# Trinity_Flight_Computer_2025-07-16.net
KiCad netlist of a schematic drawn in EasyEDA Pro
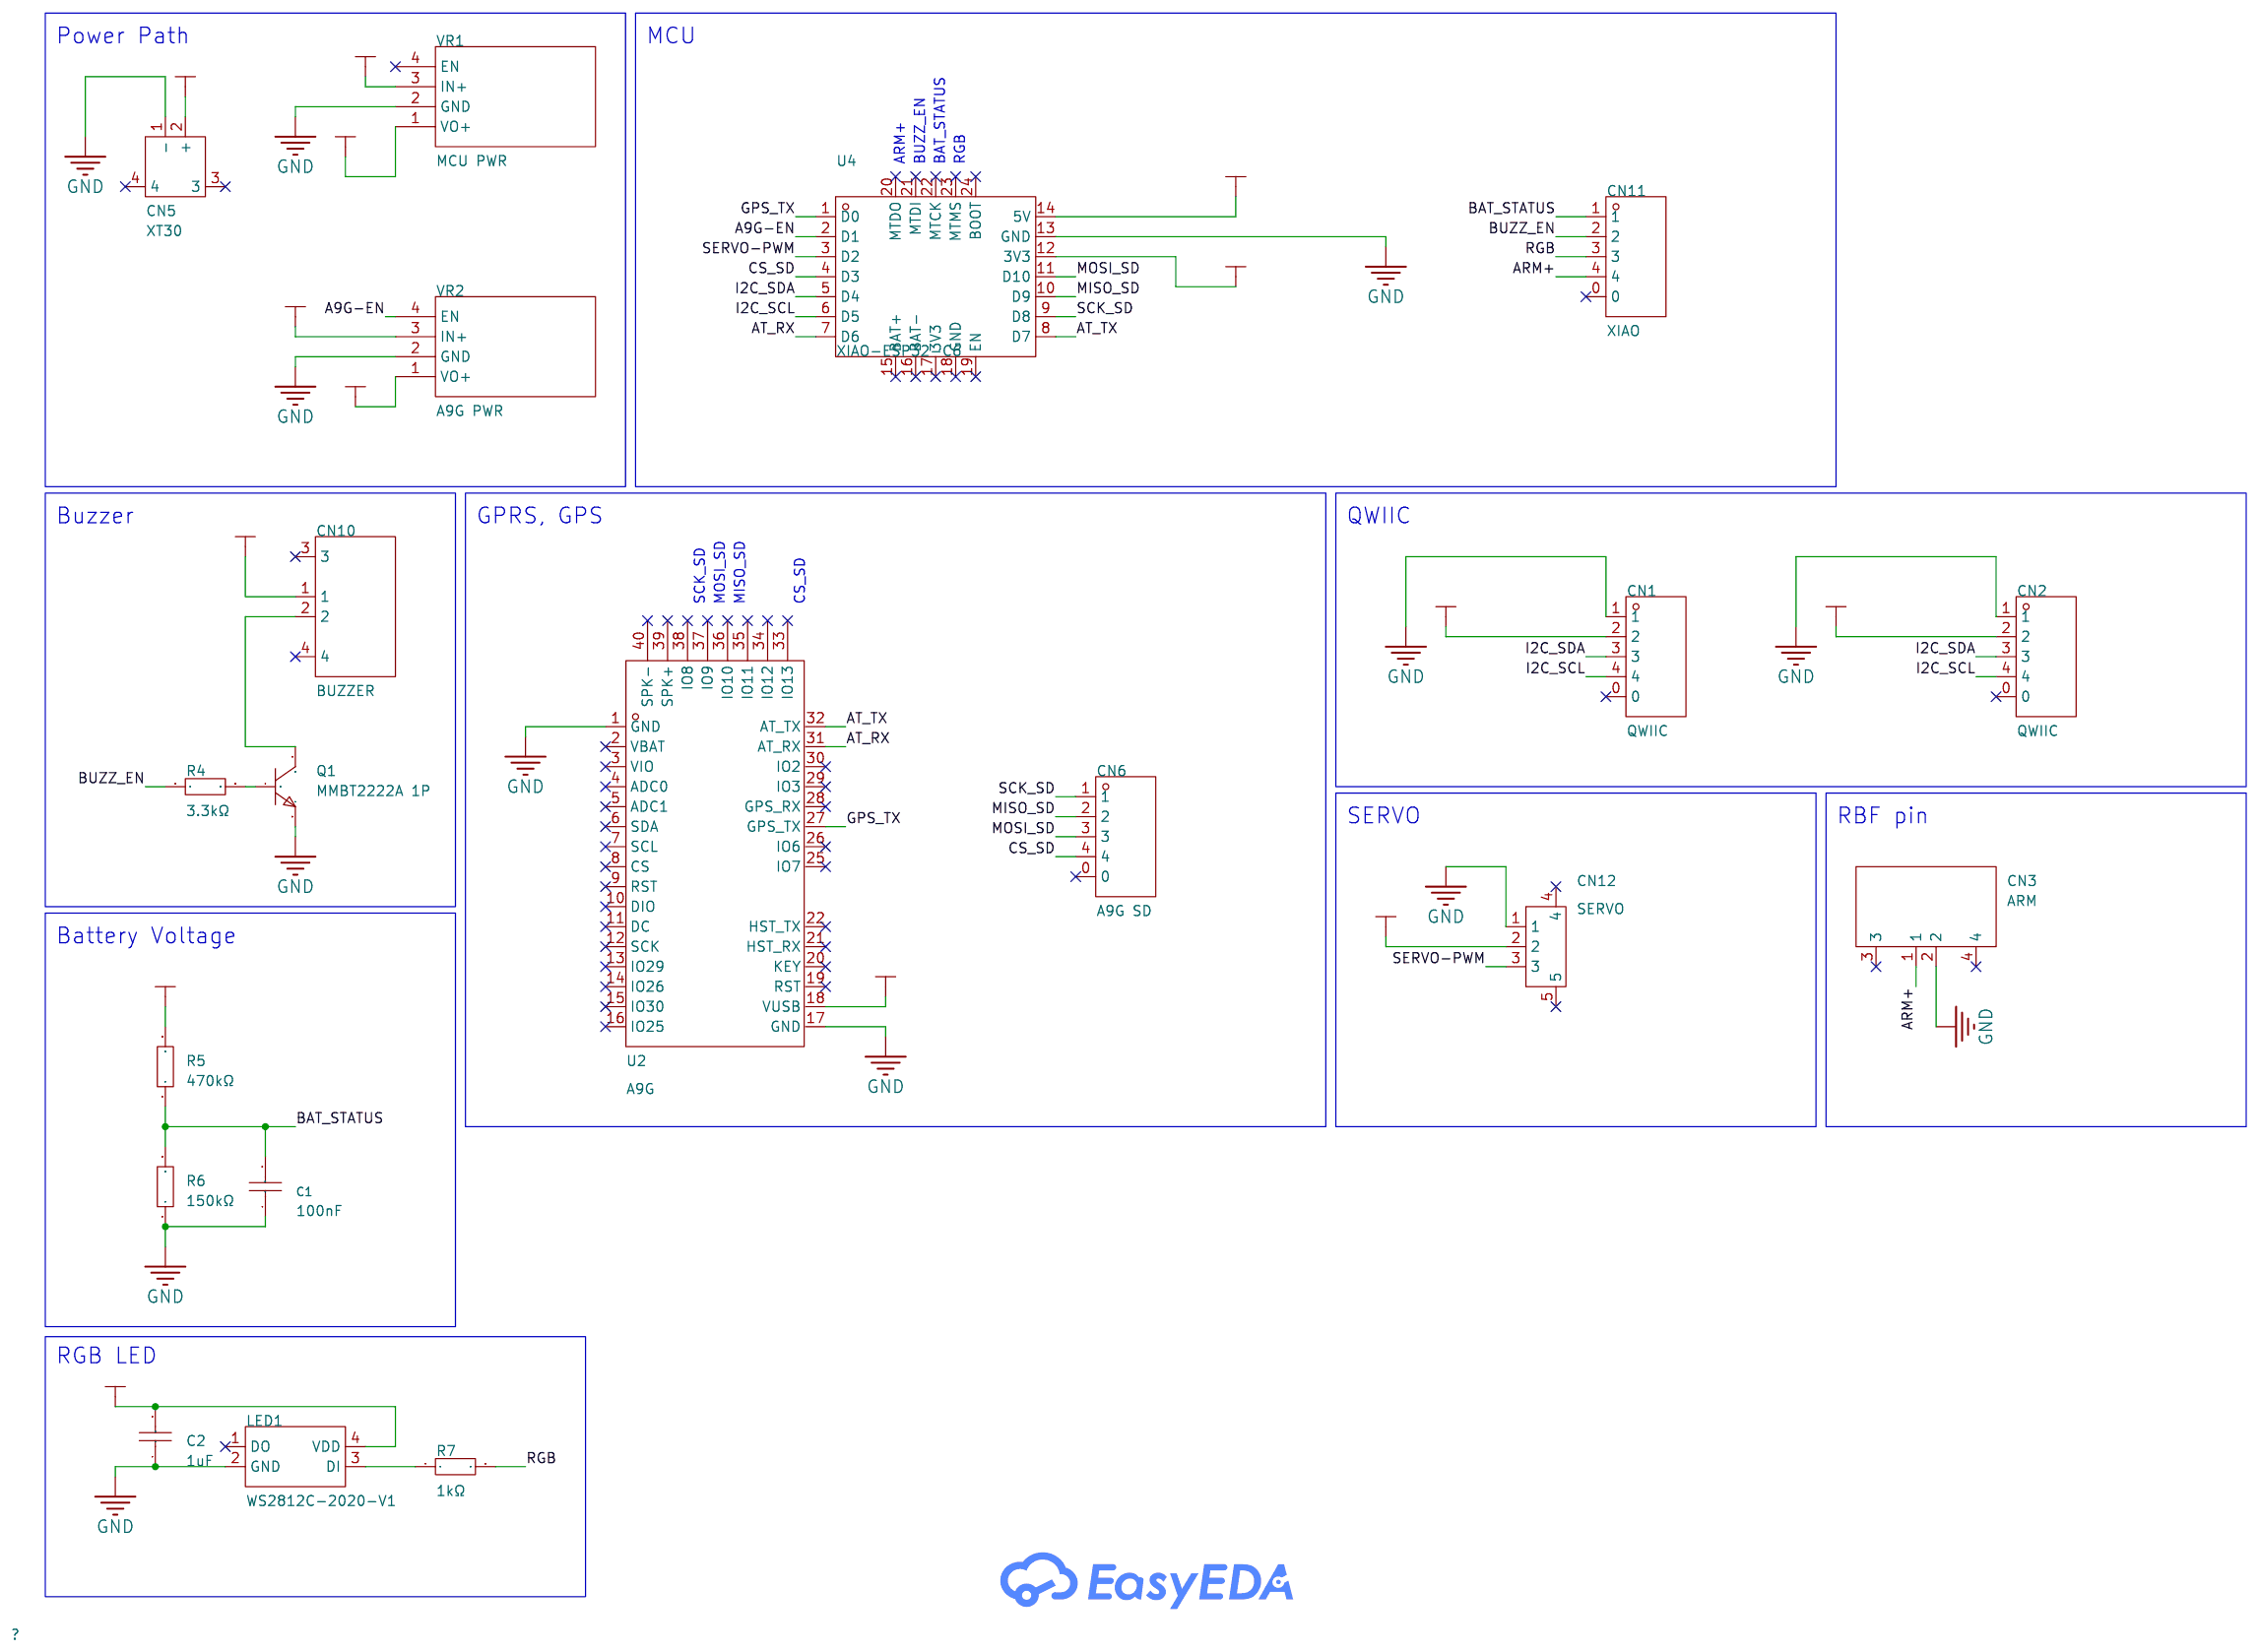
[diagram p0: schematic sheet]

(export (version "E")
  (design (tool "Eeschema 10.0.6"))
  (components
    (comp (ref "C1")
      (value "100nF")
      (footprint "easyedapro:C0603")
      (fields (field (name "Manufacturer Part") "0603B104K250CT") (field (name "Manufacturer") "Walsin(华新科)"))
      (libsource (lib "easyedapro") (part "0603B104K250"))
    )
    (comp (ref "C2")
      (value "1uF")
      (footprint "easyedapro:C0603")
      (fields (field (name "Manufacturer Part") "0603B105K160CT") (field (name "Manufacturer") "Walsin(华新科)"))
      (libsource (lib "easyedapro") (part "0603B105K160"))
    )
    (comp (ref "CN1")
      (value "QWIIC")
      (footprint "easyedapro:CONN-SMD_BM04B-SRSS-TB")
      (fields (field (name "Manufacturer Part") "BM04B-SRSS-TB(LF)(SN)") (field (name "Manufacturer") "JST"))
      (libsource (lib "easyedapro") (part "BM04B-SRSS-TB(LF)(SN)"))
    )
    (comp (ref "CN2")
      (value "QWIIC")
      (footprint "easyedapro:CONN-SMD_BM04B-SRSS-TB")
      (fields (field (name "Manufacturer Part") "BM04B-SRSS-TB(LF)(SN)") (field (name "Manufacturer") "JST"))
      (libsource (lib "easyedapro") (part "BM04B-SRSS-TB(LF)(SN)"))
    )
    (comp (ref "CN3")
      (value "ARM")
      (footprint "easyedapro:CONN-TH_BM02B-SRSS-TB-LF-SN")
      (fields (field (name "Manufacturer Part") "BM02B-SRSS-TB(LF)(SN)") (field (name "Manufacturer") "JST"))
      (libsource (lib "easyedapro") (part "BM02B-SRSS-TB (LF)(SN)"))
    )
    (comp (ref "CN5")
      (value "XT30")
      (footprint "easyedapro:CONN-TH_XT30PW-M")
      (fields (field (name "Manufacturer Part") "XT30PW-M30.G.Y") (field (name "Manufacturer") "AMASS(艾迈斯)"))
      (libsource (lib "easyedapro") (part "XT30PW-M"))
    )
    (comp (ref "CN6")
      (value "A9G SD")
      (footprint "easyedapro:CONN-SMD_BM04B-SRSS-TB")
      (fields (field (name "Manufacturer Part") "BM04B-SRSS-TB(LF)(SN)") (field (name "Manufacturer") "JST"))
      (libsource (lib "easyedapro") (part "BM04B-SRSS-TB(LF)(SN)"))
    )
    (comp (ref "CN10")
      (value "BUZZER")
      (footprint "easyedapro:CONN-TH_BM02B-SRSS-TB-LF-SN")
      (fields (field (name "Manufacturer Part") "BM02B-SRSS-TB(LF)(SN)") (field (name "Manufacturer") "JST"))
      (libsource (lib "easyedapro") (part "BM02B-SRSS-TB (LF)(SN)"))
    )
    (comp (ref "CN11")
      (value "XIAO")
      (footprint "easyedapro:CONN-SMD_BM04B-SRSS-TB")
      (fields (field (name "Manufacturer Part") "BM04B-SRSS-TB(LF)(SN)") (field (name "Manufacturer") "JST"))
      (libsource (lib "easyedapro") (part "BM04B-SRSS-TB(LF)(SN)"))
    )
    (comp (ref "CN12")
      (value "SERVO")
      (footprint "easyedapro:CONN-SMD_BM03B-SRSS-TBT-LF-SN")
      (fields (field (name "Manufacturer Part") "BM03B-SRSS-TBT(LF)(SN)") (field (name "Manufacturer") "JST"))
      (libsource (lib "easyedapro") (part "BM03B-SRSS-TBT(LF)(SN)"))
    )
    (comp (ref "LED1")
      (value "WS2812C-2020-V1")
      (footprint "easyedapro:LED-SMD_4P-L2.0-W2.0-TL_WS2812B-2020")
      (fields (field (name "Manufacturer") "worldsemi"))
      (libsource (lib "easyedapro") (part "WS2812C-2020-V1"))
    )
    (comp (ref "Q1")
      (value "MMBT2222A 1P")
      (footprint "easyedapro:SOT-23-3_L2.9-W1.3-P1.90-LS2.4-BR")
      (fields (field (name "Manufacturer") "CJ(江苏长电/长晶)"))
      (libsource (lib "easyedapro") (part "MMBT2222A_C8512"))
    )
    (comp (ref "R4")
      (value "3.3kΩ")
      (footprint "easyedapro:R0603")
      (fields (field (name "Manufacturer Part") "WR06X332JTL") (field (name "Manufacturer") "Walsin(华新科)"))
      (libsource (lib "easyedapro") (part "WR06X332JTL"))
    )
    (comp (ref "R5")
      (value "470kΩ")
      (footprint "easyedapro:R0603")
      (fields (field (name "Manufacturer Part") "WR06X4703FTL") (field (name "Manufacturer") "Walsin(华新科)"))
      (libsource (lib "easyedapro") (part "WR06X4703FTL"))
    )
    (comp (ref "R6")
      (value "150kΩ")
      (footprint "easyedapro:R0603")
      (fields (field (name "Manufacturer Part") "WR06X1503FTL") (field (name "Manufacturer") "Walsin(华新科)"))
      (libsource (lib "easyedapro") (part "WR06X1503FTL"))
    )
    (comp (ref "R7")
      (value "1kΩ")
      (footprint "easyedapro:R0603")
      (fields (field (name "Manufacturer Part") "WR06X1001FTL") (field (name "Manufacturer") "Walsin(华新科)"))
      (libsource (lib "easyedapro") (part "WR06X1001FTL"))
    )
    (comp (ref "U2")
      (value "A9G")
      (footprint "easyedapro:COMM-TH_A9G-MODULE")
      (fields (field (name "Manufacturer") "Ai-Thinker"))
      (libsource (lib "easyedapro") (part "A9G Pudding Dev Module Headers Extended"))
    )
    (comp (ref "U4")
      (value "XIAO-ESP32-C6")
      (footprint "easyedapro:XIAO-ESP32-C6")
      (libsource (lib "easyedapro") (part "XIAO-ESP32-C6 Headers Extended"))
    )
    (comp (ref "VR1")
      (value "MCU PWR")
      (footprint "easyedapro:MP2315")
      (libsource (lib "easyedapro") (part "MP2315"))
    )
    (comp (ref "VR2")
      (value "A9G PWR")
      (footprint "easyedapro:MP2315")
      (libsource (lib "easyedapro") (part "MP2315"))
    )
  )
  (nets
    (net (code "1") (name "/A9G-EN") (class "Default")
      (node (ref "U4") (pin "2") (pinfunction "D1_2") (pintype "bidirectional"))
      (node (ref "VR2") (pin "4") (pinfunction "EN_4") (pintype "unspecified"))
    )
    (net (code "2") (name "/ARM+") (class "Default")
      (node (ref "CN11") (pin "4") (pinfunction "4_4") (pintype "unspecified"))
      (node (ref "CN3") (pin "1") (pinfunction "1_1") (pintype "unspecified"))
    )
    (net (code "3") (name "/AT_RX") (class "Default")
      (node (ref "U2") (pin "31") (pinfunction "AT_RX_31") (pintype "unspecified"))
      (node (ref "U4") (pin "7") (pinfunction "D6_7") (pintype "bidirectional"))
    )
    (net (code "4") (name "/AT_TX") (class "Default")
      (node (ref "U2") (pin "32") (pinfunction "AT_TX_32") (pintype "unspecified"))
      (node (ref "U4") (pin "8") (pinfunction "D7_8") (pintype "bidirectional"))
    )
    (net (code "5") (name "/BAT_STATUS") (class "Default")
      (node (ref "C1") (pin "2") (pinfunction "2_2") (pintype "input"))
      (node (ref "CN11") (pin "1") (pinfunction "1_1") (pintype "unspecified"))
      (node (ref "R5") (pin "1") (pinfunction "1_1") (pintype "unspecified"))
      (node (ref "R6") (pin "2") (pinfunction "2_2") (pintype "unspecified"))
    )
    (net (code "6") (name "/BUZZ_EN") (class "Default")
      (node (ref "CN11") (pin "2") (pinfunction "2_2") (pintype "unspecified"))
      (node (ref "R4") (pin "1") (pinfunction "1_1") (pintype "input"))
    )
    (net (code "7") (name "/CS_SD") (class "Default")
      (node (ref "CN6") (pin "4") (pinfunction "4_4") (pintype "unspecified"))
      (node (ref "U4") (pin "4") (pinfunction "D3_4") (pintype "bidirectional"))
    )
    (net (code "8") (name "/GPS_TX") (class "Default")
      (node (ref "U2") (pin "27") (pinfunction "GPS_TX_27") (pintype "unspecified"))
      (node (ref "U4") (pin "1") (pinfunction "D0_1") (pintype "bidirectional"))
    )
    (net (code "9") (name "/I2C_SCL") (class "Default")
      (node (ref "CN1") (pin "4") (pinfunction "4_4") (pintype "unspecified"))
      (node (ref "CN2") (pin "4") (pinfunction "4_4") (pintype "unspecified"))
      (node (ref "U4") (pin "6") (pinfunction "D5_6") (pintype "bidirectional"))
    )
    (net (code "10") (name "/I2C_SDA") (class "Default")
      (node (ref "CN1") (pin "3") (pinfunction "3_3") (pintype "unspecified"))
      (node (ref "CN2") (pin "3") (pinfunction "3_3") (pintype "unspecified"))
      (node (ref "U4") (pin "5") (pinfunction "D4_5") (pintype "bidirectional"))
    )
    (net (code "11") (name "/MISO_SD") (class "Default")
      (node (ref "CN6") (pin "2") (pinfunction "2_2") (pintype "unspecified"))
      (node (ref "U4") (pin "10") (pinfunction "D9_10") (pintype "bidirectional"))
    )
    (net (code "12") (name "/MOSI_SD") (class "Default")
      (node (ref "CN6") (pin "3") (pinfunction "3_3") (pintype "unspecified"))
      (node (ref "U4") (pin "11") (pinfunction "D10_11") (pintype "bidirectional"))
    )
    (net (code "13") (name "/RGB") (class "Default")
      (node (ref "CN11") (pin "3") (pinfunction "3_3") (pintype "unspecified"))
      (node (ref "R7") (pin "2") (pinfunction "2_2") (pintype "input"))
    )
    (net (code "14") (name "/SCK_SD") (class "Default")
      (node (ref "CN6") (pin "1") (pinfunction "1_1") (pintype "unspecified"))
      (node (ref "U4") (pin "9") (pinfunction "D8_9") (pintype "bidirectional"))
    )
    (net (code "15") (name "/SERVO-PWM") (class "Default")
      (node (ref "CN12") (pin "3") (pinfunction "3_3") (pintype "unspecified"))
      (node (ref "U4") (pin "3") (pinfunction "D2_3") (pintype "bidirectional"))
    )
    (net (code "16") (name "3V3") (class "Default")
      (node (ref "CN1") (pin "2") (pinfunction "2_2") (pintype "unspecified"))
      (node (ref "CN2") (pin "2") (pinfunction "2_2") (pintype "unspecified"))
      (node (ref "U4") (pin "12") (pinfunction "3V3_12") (pintype "unspecified"))
    )
    (net (code "17") (name "5VA") (class "Default")
      (node (ref "U2") (pin "18") (pinfunction "VUSB_18") (pintype "unspecified"))
      (node (ref "VR2") (pin "1") (pinfunction "VO+_1") (pintype "unspecified"))
    )
    (net (code "18") (name "5VM") (class "Default")
      (node (ref "C2") (pin "2") (pinfunction "2_2") (pintype "input"))
      (node (ref "CN12") (pin "2") (pinfunction "2_2") (pintype "unspecified"))
      (node (ref "LED1") (pin "4") (pinfunction "VDD_4") (pintype "unspecified"))
      (node (ref "U4") (pin "14") (pinfunction "5V_14") (pintype "unspecified"))
      (node (ref "VR1") (pin "1") (pinfunction "VO+_1") (pintype "unspecified"))
    )
    (net (code "19") (name "7V4") (class "Default")
      (node (ref "CN10") (pin "1") (pinfunction "1_1") (pintype "unspecified"))
      (node (ref "CN5") (pin "2") (pinfunction "+_2") (pintype "unspecified"))
      (node (ref "R5") (pin "2") (pinfunction "2_2") (pintype "unspecified"))
      (node (ref "VR1") (pin "3") (pinfunction "IN+_3") (pintype "unspecified"))
      (node (ref "VR2") (pin "3") (pinfunction "IN+_3") (pintype "unspecified"))
    )
    (net (code "20") (name "GND") (class "Default")
      (node (ref "C1") (pin "1") (pinfunction "1_1") (pintype "input"))
      (node (ref "C2") (pin "1") (pinfunction "1_1") (pintype "input"))
      (node (ref "CN1") (pin "1") (pinfunction "1_1") (pintype "unspecified"))
      (node (ref "CN12") (pin "1") (pinfunction "1_1") (pintype "unspecified"))
      (node (ref "CN2") (pin "1") (pinfunction "1_1") (pintype "unspecified"))
      (node (ref "CN3") (pin "2") (pinfunction "2_2") (pintype "unspecified"))
      (node (ref "CN5") (pin "1") (pinfunction "-_1") (pintype "unspecified"))
      (node (ref "LED1") (pin "2") (pinfunction "GND_2") (pintype "unspecified"))
      (node (ref "Q1") (pin "2") (pinfunction "E_2") (pintype "unspecified"))
      (node (ref "R6") (pin "1") (pinfunction "1_1") (pintype "unspecified"))
      (node (ref "U2") (pin "1") (pinfunction "GND_1") (pintype "unspecified"))
      (node (ref "U2") (pin "17") (pinfunction "GND_17") (pintype "unspecified"))
      (node (ref "U4") (pin "13") (pinfunction "GND_13") (pintype "unspecified"))
      (node (ref "VR1") (pin "2") (pinfunction "GND_2") (pintype "unspecified"))
      (node (ref "VR2") (pin "2") (pinfunction "GND_2") (pintype "unspecified"))
    )
    (net (code "21") (name "Net-(LED1-DI)") (class "Default")
      (node (ref "LED1") (pin "3") (pinfunction "DI_3") (pintype "unspecified"))
      (node (ref "R7") (pin "1") (pinfunction "1_1") (pintype "input"))
    )
    (net (code "22") (name "Net-(Q1-B)") (class "Default")
      (node (ref "Q1") (pin "1") (pinfunction "B_1") (pintype "unspecified"))
      (node (ref "R4") (pin "2") (pinfunction "2_2") (pintype "input"))
    )
    (net (code "23") (name "Net-(Q1-C)") (class "Default")
      (node (ref "CN10") (pin "2") (pinfunction "2_2") (pintype "unspecified"))
      (node (ref "Q1") (pin "3") (pinfunction "C_3") (pintype "unspecified"))
    )
    (net (code "24") (name "unconnected-(CN1-Pad0)") (class "Default")
      (node (ref "CN1") (pin "0") (pinfunction "0_0") (pintype "unspecified+no_connect"))
    )
    (net (code "25") (name "unconnected-(CN2-Pad0)") (class "Default")
      (node (ref "CN2") (pin "0") (pinfunction "0_0") (pintype "unspecified+no_connect"))
    )
    (net (code "26") (name "unconnected-(CN3-Pad3)") (class "Default")
      (node (ref "CN3") (pin "3") (pinfunction "3_3") (pintype "unspecified+no_connect"))
    )
    (net (code "27") (name "unconnected-(CN3-Pad4)") (class "Default")
      (node (ref "CN3") (pin "4") (pinfunction "4_4") (pintype "unspecified+no_connect"))
    )
    (net (code "28") (name "unconnected-(CN5-Pad3)") (class "Default")
      (node (ref "CN5") (pin "3") (pinfunction "3_3") (pintype "unspecified+no_connect"))
    )
    (net (code "29") (name "unconnected-(CN5-Pad4)") (class "Default")
      (node (ref "CN5") (pin "4") (pinfunction "4_4") (pintype "unspecified+no_connect"))
    )
    (net (code "30") (name "unconnected-(CN6-Pad0)") (class "Default")
      (node (ref "CN6") (pin "0") (pinfunction "0_0") (pintype "unspecified+no_connect"))
    )
    (net (code "31") (name "unconnected-(CN10-Pad3)") (class "Default")
      (node (ref "CN10") (pin "3") (pinfunction "3_3") (pintype "unspecified+no_connect"))
    )
    (net (code "32") (name "unconnected-(CN10-Pad4)") (class "Default")
      (node (ref "CN10") (pin "4") (pinfunction "4_4") (pintype "unspecified+no_connect"))
    )
    (net (code "33") (name "unconnected-(CN11-Pad0)") (class "Default")
      (node (ref "CN11") (pin "0") (pinfunction "0_0") (pintype "unspecified+no_connect"))
    )
    (net (code "34") (name "unconnected-(CN12-Pad4)") (class "Default")
      (node (ref "CN12") (pin "4") (pinfunction "4_4") (pintype "unspecified+no_connect"))
    )
    (net (code "35") (name "unconnected-(CN12-Pad5)") (class "Default")
      (node (ref "CN12") (pin "5") (pinfunction "5_5") (pintype "unspecified+no_connect"))
    )
    (net (code "36") (name "unconnected-(LED1-DO-Pad1)") (class "Default")
      (node (ref "LED1") (pin "1") (pinfunction "DO_1") (pintype "unspecified+no_connect"))
    )
    (net (code "37") (name "unconnected-(U2-ADC0-Pad4)") (class "Default")
      (node (ref "U2") (pin "4") (pinfunction "ADC0_4") (pintype "unspecified+no_connect"))
    )
    (net (code "38") (name "unconnected-(U2-ADC1-Pad5)") (class "Default")
      (node (ref "U2") (pin "5") (pinfunction "ADC1_5") (pintype "unspecified+no_connect"))
    )
    (net (code "39") (name "unconnected-(U2-CS-Pad8)") (class "Default")
      (node (ref "U2") (pin "8") (pinfunction "CS_8") (pintype "unspecified+no_connect"))
    )
    (net (code "40") (name "unconnected-(U2-DC-Pad11)") (class "Default")
      (node (ref "U2") (pin "11") (pinfunction "DC_11") (pintype "unspecified+no_connect"))
    )
    (net (code "41") (name "unconnected-(U2-DIO-Pad10)") (class "Default")
      (node (ref "U2") (pin "10") (pinfunction "DIO_10") (pintype "unspecified+no_connect"))
    )
    (net (code "42") (name "unconnected-(U2-GPS_RX-Pad28)") (class "Default")
      (node (ref "U2") (pin "28") (pinfunction "GPS_RX_28") (pintype "unspecified+no_connect"))
    )
    (net (code "43") (name "unconnected-(U2-HST_RX-Pad21)") (class "Default")
      (node (ref "U2") (pin "21") (pinfunction "HST_RX_21") (pintype "unspecified+no_connect"))
    )
    (net (code "44") (name "unconnected-(U2-HST_TX-Pad22)") (class "Default")
      (node (ref "U2") (pin "22") (pinfunction "HST_TX_22") (pintype "unspecified+no_connect"))
    )
    (net (code "45") (name "unconnected-(U2-IO2-Pad30)") (class "Default")
      (node (ref "U2") (pin "30") (pinfunction "IO2_30") (pintype "unspecified+no_connect"))
    )
    (net (code "46") (name "unconnected-(U2-IO3-Pad29)") (class "Default")
      (node (ref "U2") (pin "29") (pinfunction "IO3_29") (pintype "unspecified+no_connect"))
    )
    (net (code "47") (name "unconnected-(U2-IO6-Pad26)") (class "Default")
      (node (ref "U2") (pin "26") (pinfunction "IO6_26") (pintype "unspecified+no_connect"))
    )
    (net (code "48") (name "unconnected-(U2-IO7-Pad25)") (class "Default")
      (node (ref "U2") (pin "25") (pinfunction "IO7_25") (pintype "unspecified+no_connect"))
    )
    (net (code "49") (name "unconnected-(U2-IO8-Pad38)") (class "Default")
      (node (ref "U2") (pin "38") (pinfunction "IO8_38") (pintype "input+no_connect"))
    )
    (net (code "50") (name "unconnected-(U2-IO9-Pad37)") (class "Default")
      (node (ref "U2") (pin "37") (pinfunction "IO9_37") (pintype "input+no_connect"))
    )
    (net (code "51") (name "unconnected-(U2-IO10-Pad36)") (class "Default")
      (node (ref "U2") (pin "36") (pinfunction "IO10_36") (pintype "input+no_connect"))
    )
    (net (code "52") (name "unconnected-(U2-IO11-Pad35)") (class "Default")
      (node (ref "U2") (pin "35") (pinfunction "IO11_35") (pintype "input+no_connect"))
    )
    (net (code "53") (name "unconnected-(U2-IO12-Pad34)") (class "Default")
      (node (ref "U2") (pin "34") (pinfunction "IO12_34") (pintype "input+no_connect"))
    )
    (net (code "54") (name "unconnected-(U2-IO13-Pad33)") (class "Default")
      (node (ref "U2") (pin "33") (pinfunction "IO13_33") (pintype "input+no_connect"))
    )
    (net (code "55") (name "unconnected-(U2-IO25-Pad16)") (class "Default")
      (node (ref "U2") (pin "16") (pinfunction "IO25_16") (pintype "unspecified+no_connect"))
    )
    (net (code "56") (name "unconnected-(U2-IO26-Pad14)") (class "Default")
      (node (ref "U2") (pin "14") (pinfunction "IO26_14") (pintype "unspecified+no_connect"))
    )
    (net (code "57") (name "unconnected-(U2-IO29-Pad13)") (class "Default")
      (node (ref "U2") (pin "13") (pinfunction "IO29_13") (pintype "unspecified+no_connect"))
    )
    (net (code "58") (name "unconnected-(U2-IO30-Pad15)") (class "Default")
      (node (ref "U2") (pin "15") (pinfunction "IO30_15") (pintype "unspecified+no_connect"))
    )
    (net (code "59") (name "unconnected-(U2-KEY-Pad20)") (class "Default")
      (node (ref "U2") (pin "20") (pinfunction "KEY_20") (pintype "unspecified+no_connect"))
    )
    (net (code "60") (name "unconnected-(U2-RST-Pad9)") (class "Default")
      (node (ref "U2") (pin "9") (pinfunction "RST_9") (pintype "unspecified+no_connect"))
    )
    (net (code "61") (name "unconnected-(U2-RST-Pad19)") (class "Default")
      (node (ref "U2") (pin "19") (pinfunction "RST_19") (pintype "unspecified+no_connect"))
    )
    (net (code "62") (name "unconnected-(U2-SCK-Pad12)") (class "Default")
      (node (ref "U2") (pin "12") (pinfunction "SCK_12") (pintype "unspecified+no_connect"))
    )
    (net (code "63") (name "unconnected-(U2-SCL-Pad7)") (class "Default")
      (node (ref "U2") (pin "7") (pinfunction "SCL_7") (pintype "unspecified+no_connect"))
    )
    (net (code "64") (name "unconnected-(U2-SDA-Pad6)") (class "Default")
      (node (ref "U2") (pin "6") (pinfunction "SDA_6") (pintype "unspecified+no_connect"))
    )
    (net (code "65") (name "unconnected-(U2-SPK+-Pad39)") (class "Default")
      (node (ref "U2") (pin "39") (pinfunction "SPK+_39") (pintype "input+no_connect"))
    )
    (net (code "66") (name "unconnected-(U2-SPK--Pad40)") (class "Default")
      (node (ref "U2") (pin "40") (pinfunction "SPK-_40") (pintype "input+no_connect"))
    )
    (net (code "67") (name "unconnected-(U2-VBAT-Pad2)") (class "Default")
      (node (ref "U2") (pin "2") (pinfunction "VBAT_2") (pintype "unspecified+no_connect"))
    )
    (net (code "68") (name "unconnected-(U2-VIO-Pad3)") (class "Default")
      (node (ref "U2") (pin "3") (pinfunction "VIO_3") (pintype "unspecified+no_connect"))
    )
    (net (code "69") (name "unconnected-(U4-3V3-Pad17)") (class "Default")
      (node (ref "U4") (pin "17") (pinfunction "3V3_17") (pintype "unspecified+no_connect"))
    )
    (net (code "70") (name "unconnected-(U4-BAT+-Pad15)") (class "Default")
      (node (ref "U4") (pin "15") (pinfunction "BAT+_15") (pintype "unspecified+no_connect"))
    )
    (net (code "71") (name "unconnected-(U4-BAT--Pad16)") (class "Default")
      (node (ref "U4") (pin "16") (pinfunction "BAT-_16") (pintype "unspecified+no_connect"))
    )
    (net (code "72") (name "unconnected-(U4-BOOT-Pad24)") (class "Default")
      (node (ref "U4") (pin "24") (pinfunction "BOOT_24") (pintype "input+no_connect"))
    )
    (net (code "73") (name "unconnected-(U4-EN-Pad19)") (class "Default")
      (node (ref "U4") (pin "19") (pinfunction "EN_19") (pintype "input+no_connect"))
    )
    (net (code "74") (name "unconnected-(U4-GND-Pad18)") (class "Default")
      (node (ref "U4") (pin "18") (pinfunction "GND_18") (pintype "unspecified+no_connect"))
    )
    (net (code "75") (name "unconnected-(U4-MTCK-Pad22)") (class "Default")
      (node (ref "U4") (pin "22") (pinfunction "MTCK_22") (pintype "bidirectional+no_connect"))
    )
    (net (code "76") (name "unconnected-(U4-MTDI-Pad21)") (class "Default")
      (node (ref "U4") (pin "21") (pinfunction "MTDI_21") (pintype "bidirectional+no_connect"))
    )
    (net (code "77") (name "unconnected-(U4-MTDO-Pad20)") (class "Default")
      (node (ref "U4") (pin "20") (pinfunction "MTDO_20") (pintype "bidirectional+no_connect"))
    )
    (net (code "78") (name "unconnected-(U4-MTMS-Pad23)") (class "Default")
      (node (ref "U4") (pin "23") (pinfunction "MTMS_23") (pintype "bidirectional+no_connect"))
    )
    (net (code "79") (name "unconnected-(VR1-EN-Pad4)") (class "Default")
      (node (ref "VR1") (pin "4") (pinfunction "EN_4") (pintype "unspecified+no_connect"))
    )
  )
)
